# design.net
KiCad netlist of a schematic drawn in Altium Designer
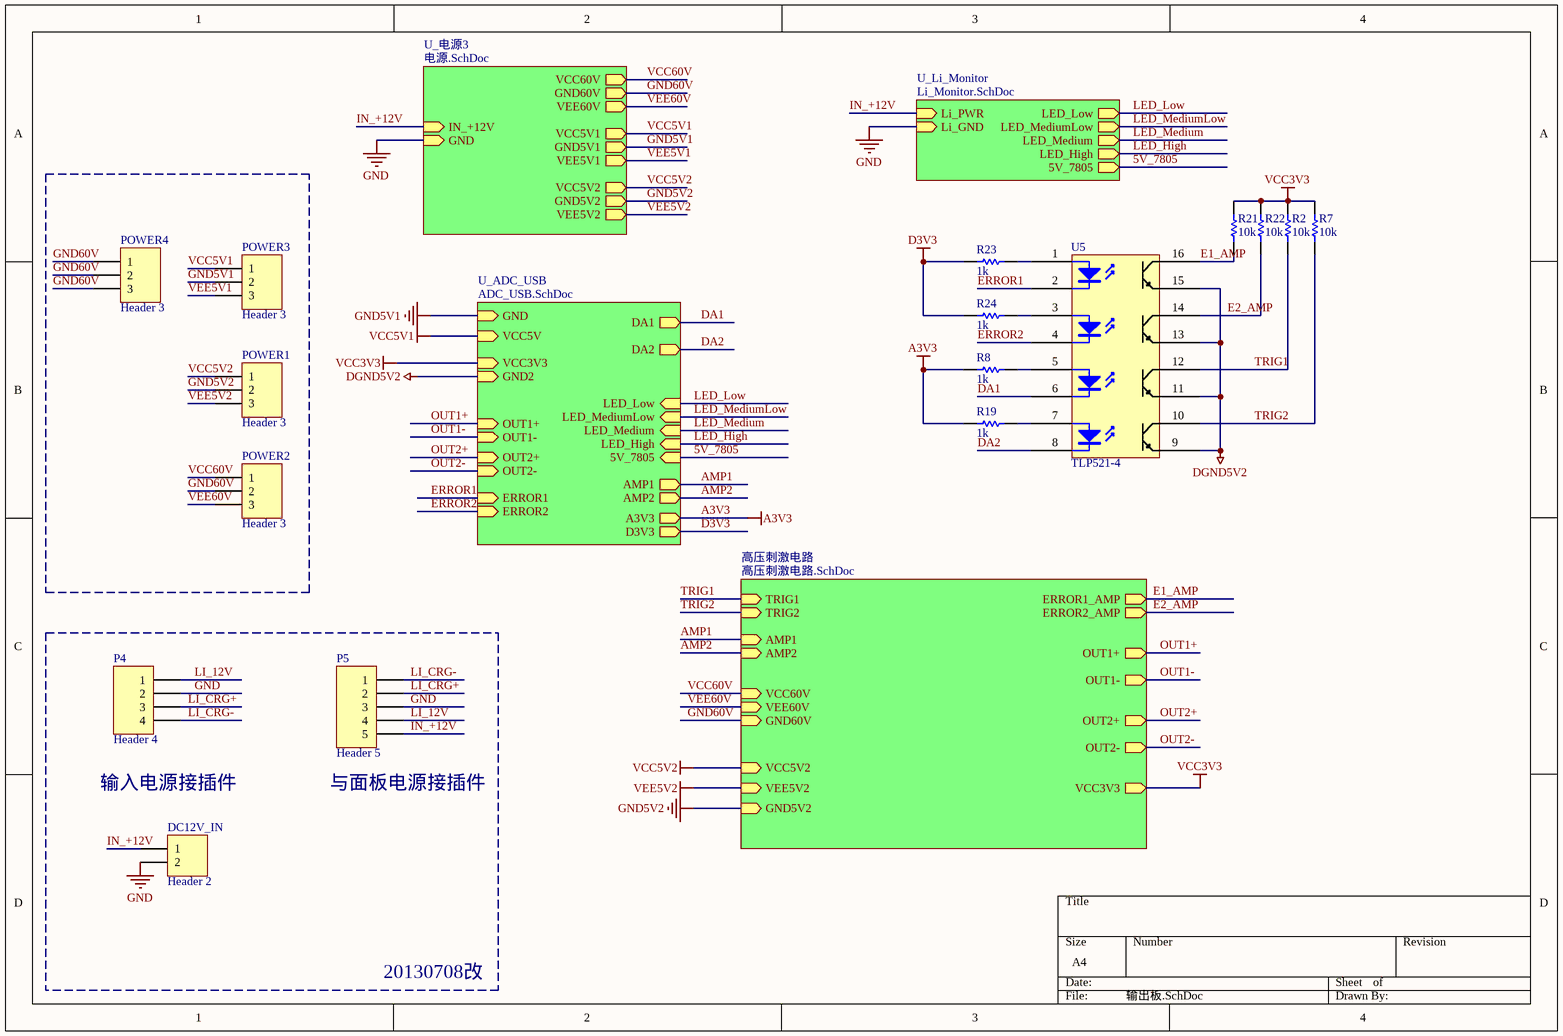
[diagram p0: 输出板.SchDoc]

(export (version "E")
  (design (tool "Eeschema 10.0.6"))
  (components
    (comp (ref "DC12V_IN")
      (value "Header 2")
      (footprint "HDR1X2")
      (description "Header, 2-Pin")
      (fields (field (name "PUBLISHER") "Altium Limited"))
      (libsource (lib "Miscellaneous Connectors") (part "Header 2"))
    )
    (comp (ref "P4")
      (value "Header 4")
      (footprint "Power-4P")
      (description "Header, 4-Pin")
      (fields (field (name "PUBLISHER") "Altium Limited"))
      (libsource (lib "Miscellaneous Connectors") (part "Header 4"))
    )
    (comp (ref "P5")
      (value "Header 5")
      (footprint "Power-5P")
      (description "Header, 5-Pin")
      (fields (field (name "PUBLISHER") "Altium Limited"))
      (libsource (lib "Miscellaneous Connectors") (part "Header 5"))
    )
    (comp (ref "POWER1")
      (value "Header 3")
      (footprint "HDR1X3")
      (description "Header, 3-Pin")
      (fields (field (name "PUBLISHER") "Altium Limited"))
      (libsource (lib "Miscellaneous Connectors") (part "Header 3"))
    )
    (comp (ref "POWER2")
      (value "Header 3")
      (footprint "HDR1X3")
      (description "Header, 3-Pin")
      (fields (field (name "PUBLISHER") "Altium Limited"))
      (libsource (lib "Miscellaneous Connectors") (part "Header 3"))
    )
    (comp (ref "POWER3")
      (value "Header 3")
      (footprint "HDR1X3")
      (description "Header, 3-Pin")
      (fields (field (name "PUBLISHER") "Altium Limited"))
      (libsource (lib "Miscellaneous Connectors") (part "Header 3"))
    )
    (comp (ref "POWER4")
      (value "Header 3")
      (footprint "HDR1X3")
      (description "Header, 3-Pin")
      (fields (field (name "PUBLISHER") "Altium Limited"))
      (libsource (lib "Miscellaneous Connectors") (part "Header 3"))
    )
    (comp (ref "R2")
      (value "10k")
      (footprint "R0603")
      (description "Resistor")
      (fields (field (name "PUBLISHER") "Altium Limited"))
      (libsource (lib "Miscellaneous Devices") (part "Res1"))
    )
    (comp (ref "R7")
      (value "10k")
      (footprint "R0603")
      (description "Resistor")
      (fields (field (name "PUBLISHER") "Altium Limited"))
      (libsource (lib "Miscellaneous Devices") (part "Res1"))
    )
    (comp (ref "R8")
      (value "1k")
      (footprint "R0603")
      (description "Resistor")
      (fields (field (name "PUBLISHER") "Altium Limited"))
      (libsource (lib "Miscellaneous Devices") (part "Res1"))
    )
    (comp (ref "R19")
      (value "1k")
      (footprint "R0603")
      (description "Resistor")
      (fields (field (name "PUBLISHER") "Altium Limited"))
      (libsource (lib "Miscellaneous Devices") (part "Res1"))
    )
    (comp (ref "R21")
      (value "10k")
      (footprint "R0603")
      (description "Resistor")
      (fields (field (name "PUBLISHER") "Altium Limited"))
      (libsource (lib "Miscellaneous Devices") (part "Res1"))
    )
    (comp (ref "R22")
      (value "10k")
      (footprint "R0603")
      (description "Resistor")
      (fields (field (name "PUBLISHER") "Altium Limited"))
      (libsource (lib "Miscellaneous Devices") (part "Res1"))
    )
    (comp (ref "R23")
      (value "1k")
      (footprint "R0603")
      (description "Resistor")
      (fields (field (name "PUBLISHER") "Altium Limited"))
      (libsource (lib "Miscellaneous Devices") (part "Res1"))
    )
    (comp (ref "R24")
      (value "1k")
      (footprint "R0603")
      (description "Resistor")
      (fields (field (name "PUBLISHER") "Altium Limited"))
      (libsource (lib "Miscellaneous Devices") (part "Res1"))
    )
    (comp (ref "U5") (value "TLP521-4") (footprint "DIP-16") (libsource (lib "常用器件原理图库") (part "TLP521-4")))
  )
  (nets
    (net (code "4") (name "/DA1") (class "Default")
      (node (ref "U5") (pin "6") (pinfunction "6_6") (pintype "passive"))
    )
    (net (code "5") (name "/DA2") (class "Default")
      (node (ref "U5") (pin "8") (pinfunction "8_8") (pintype "passive"))
    )
    (net (code "6") (name "/E1_AMP") (class "Default")
      (node (ref "R21") (pin "2") (pinfunction "2_2") (pintype "passive"))
      (node (ref "U5") (pin "16") (pinfunction "16_16") (pintype "passive"))
    )
    (net (code "7") (name "/E2_AMP") (class "Default")
      (node (ref "R22") (pin "1") (pinfunction "1_1") (pintype "passive"))
      (node (ref "U5") (pin "14") (pinfunction "14_14") (pintype "passive"))
    )
    (net (code "8") (name "/ERROR1") (class "Default")
      (node (ref "U5") (pin "2") (pinfunction "2_2") (pintype "passive"))
    )
    (net (code "9") (name "/ERROR2") (class "Default")
      (node (ref "U5") (pin "4") (pinfunction "4_4") (pintype "passive"))
    )
    (net (code "10") (name "/GND60V") (class "Default")
      (node (ref "POWER2") (pin "2") (pinfunction "2_2") (pintype "passive"))
      (node (ref "POWER4") (pin "1") (pinfunction "1_1") (pintype "passive"))
      (node (ref "POWER4") (pin "2") (pinfunction "2_2") (pintype "passive"))
      (node (ref "POWER4") (pin "3") (pinfunction "3_3") (pintype "passive"))
    )
    (net (code "11") (name "/IN_+12V") (class "Default")
      (node (ref "DC12V_IN") (pin "1") (pinfunction "1_1") (pintype "passive"))
      (node (ref "P5") (pin "5") (pinfunction "5_5") (pintype "passive"))
    )
    (net (code "16") (name "/LI_12V") (class "Default")
      (node (ref "P4") (pin "1") (pinfunction "1_1") (pintype "passive"))
      (node (ref "P5") (pin "4") (pinfunction "4_4") (pintype "passive"))
    )
    (net (code "17") (name "/LI_CRG+") (class "Default")
      (node (ref "P4") (pin "3") (pinfunction "3_3") (pintype "passive"))
      (node (ref "P5") (pin "2") (pinfunction "2_2") (pintype "passive"))
    )
    (net (code "18") (name "/LI_CRG-") (class "Default")
      (node (ref "P4") (pin "4") (pinfunction "4_4") (pintype "passive"))
      (node (ref "P5") (pin "1") (pinfunction "1_1") (pintype "passive"))
    )
    (net (code "23") (name "/TRIG1") (class "Default")
      (node (ref "R2") (pin "2") (pinfunction "2_2") (pintype "passive"))
      (node (ref "U5") (pin "12") (pinfunction "12_12") (pintype "passive"))
    )
    (net (code "24") (name "/TRIG2") (class "Default")
      (node (ref "R7") (pin "1") (pinfunction "1_1") (pintype "passive"))
      (node (ref "U5") (pin "10") (pinfunction "10_10") (pintype "passive"))
    )
    (net (code "25") (name "/VCC60V") (class "Default")
      (node (ref "POWER2") (pin "1") (pinfunction "1_1") (pintype "passive"))
    )
    (net (code "26") (name "/VEE5V1") (class "Default")
      (node (ref "POWER3") (pin "3") (pinfunction "3_3") (pintype "passive"))
    )
    (net (code "27") (name "/VEE60V") (class "Default")
      (node (ref "POWER2") (pin "3") (pinfunction "3_3") (pintype "passive"))
    )
    (net (code "28") (name "A3V3") (class "Default")
      (node (ref "R19") (pin "1") (pinfunction "1_1") (pintype "passive"))
      (node (ref "R8") (pin "1") (pinfunction "1_1") (pintype "passive"))
    )
    (net (code "29") (name "D3V3") (class "Default")
      (node (ref "R23") (pin "1") (pinfunction "1_1") (pintype "passive"))
      (node (ref "R24") (pin "1") (pinfunction "1_1") (pintype "passive"))
    )
    (net (code "30") (name "DGND5V2") (class "Default")
      (node (ref "U5") (pin "11") (pinfunction "11_11") (pintype "passive"))
      (node (ref "U5") (pin "13") (pinfunction "13_13") (pintype "passive"))
      (node (ref "U5") (pin "15") (pinfunction "15_15") (pintype "passive"))
      (node (ref "U5") (pin "9") (pinfunction "9_9") (pintype "passive"))
    )
    (net (code "31") (name "GND") (class "Default")
      (node (ref "DC12V_IN") (pin "2") (pinfunction "2_2") (pintype "passive"))
      (node (ref "P4") (pin "2") (pinfunction "2_2") (pintype "passive"))
      (node (ref "P5") (pin "3") (pinfunction "3_3") (pintype "passive"))
    )
    (net (code "32") (name "GND5V1") (class "Default")
      (node (ref "POWER3") (pin "2") (pinfunction "2_2") (pintype "passive"))
    )
    (net (code "33") (name "GND5V2") (class "Default")
      (node (ref "POWER1") (pin "2") (pinfunction "2_2") (pintype "passive"))
    )
    (net (code "34") (name "Net-(R8-Pad2)") (class "Default")
      (node (ref "R8") (pin "2") (pinfunction "2_2") (pintype "passive"))
      (node (ref "U5") (pin "5") (pinfunction "5_5") (pintype "passive"))
    )
    (net (code "35") (name "Net-(R19-Pad2)") (class "Default")
      (node (ref "R19") (pin "2") (pinfunction "2_2") (pintype "passive"))
      (node (ref "U5") (pin "7") (pinfunction "7_7") (pintype "passive"))
    )
    (net (code "36") (name "Net-(R23-Pad2)") (class "Default")
      (node (ref "R23") (pin "2") (pinfunction "2_2") (pintype "passive"))
      (node (ref "U5") (pin "1") (pinfunction "1_1") (pintype "passive"))
    )
    (net (code "37") (name "Net-(R24-Pad2)") (class "Default")
      (node (ref "R24") (pin "2") (pinfunction "2_2") (pintype "passive"))
      (node (ref "U5") (pin "3") (pinfunction "3_3") (pintype "passive"))
    )
    (net (code "38") (name "VCC3V3") (class "Default")
      (node (ref "R2") (pin "1") (pinfunction "1_1") (pintype "passive"))
      (node (ref "R21") (pin "1") (pinfunction "1_1") (pintype "passive"))
      (node (ref "R22") (pin "2") (pinfunction "2_2") (pintype "passive"))
      (node (ref "R7") (pin "2") (pinfunction "2_2") (pintype "passive"))
    )
    (net (code "39") (name "VCC5V1") (class "Default")
      (node (ref "POWER3") (pin "1") (pinfunction "1_1") (pintype "passive"))
    )
    (net (code "40") (name "VCC5V2") (class "Default")
      (node (ref "POWER1") (pin "1") (pinfunction "1_1") (pintype "passive"))
    )
    (net (code "41") (name "VEE5V2") (class "Default")
      (node (ref "POWER1") (pin "3") (pinfunction "3_3") (pintype "passive"))
    )
  )
)
